# Li_Test.net
KiCad netlist of a schematic drawn in Altium Designer
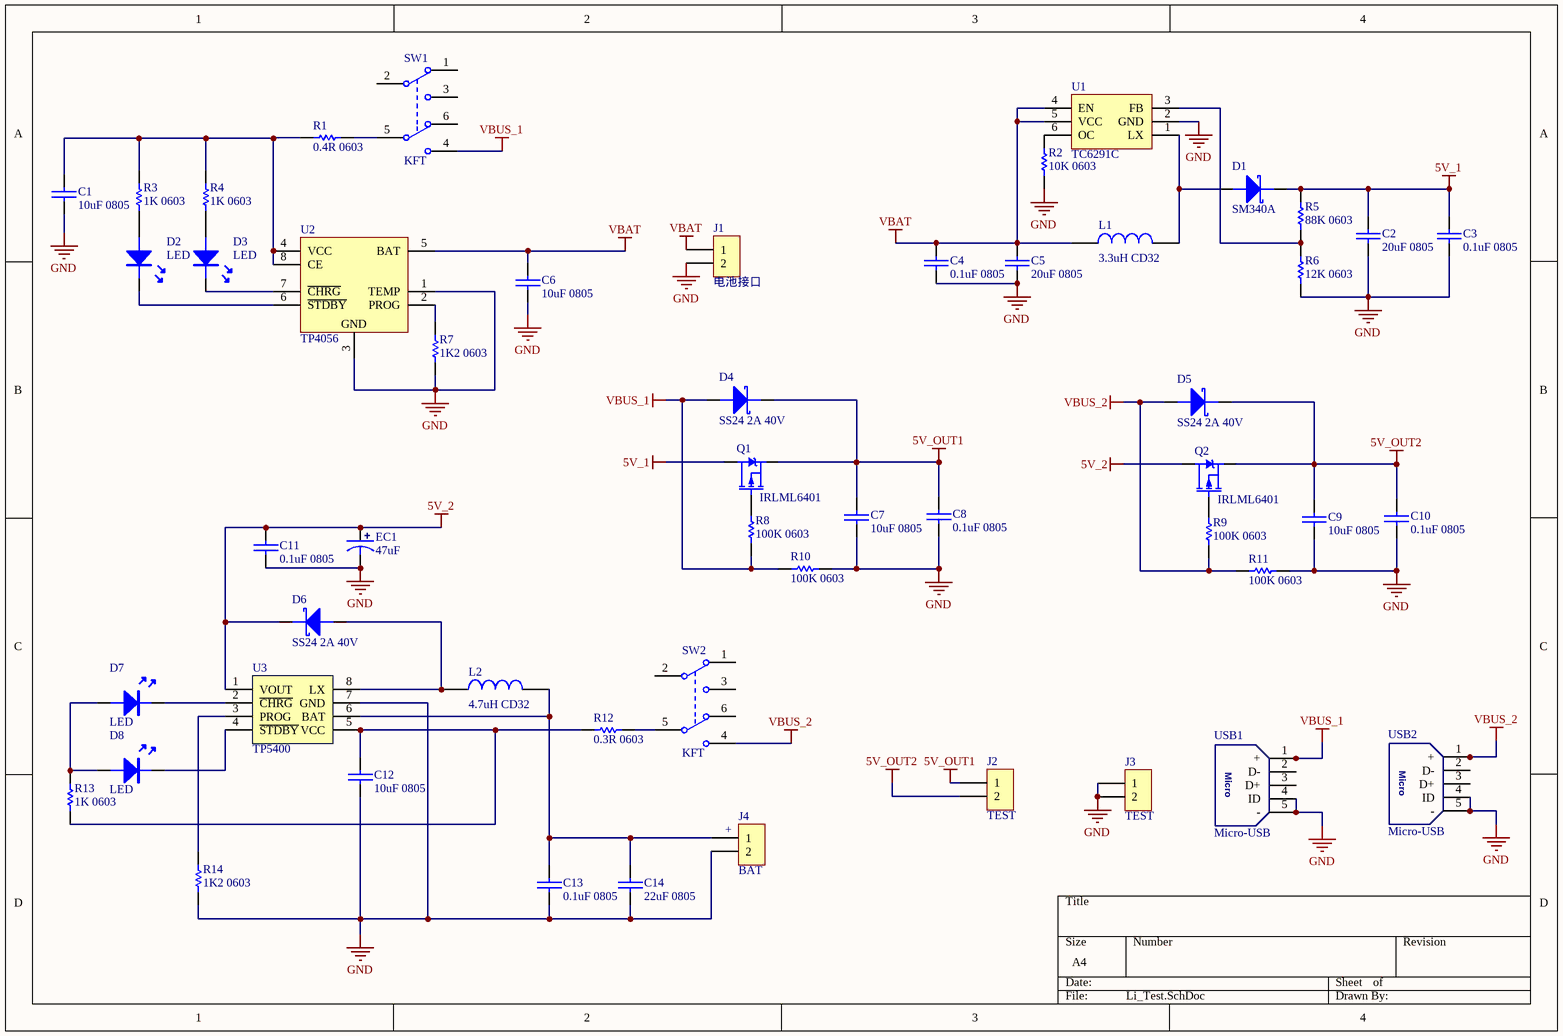
[diagram p0: Li_Test.SchDoc]

(export (version "E")
  (design (tool "Eeschema 10.0.6"))
  (components
    (comp (ref "C1")
      (value "10uF 0805")
      (footprint "0805C")
      (description "无极性电容")
      (libsource (lib "电容") (part "CAP"))
    )
    (comp (ref "C2")
      (value "20uF 0805")
      (footprint "0805C")
      (description "无极性电容")
      (libsource (lib "电容") (part "CAP"))
    )
    (comp (ref "C3")
      (value "0.1uF 0805")
      (footprint "0805C")
      (description "无极性电容")
      (libsource (lib "电容") (part "CAP"))
    )
    (comp (ref "C4")
      (value "0.1uF 0805")
      (footprint "0805C")
      (description "无极性电容")
      (libsource (lib "电容") (part "CAP"))
    )
    (comp (ref "C5")
      (value "20uF 0805")
      (footprint "0805C")
      (description "无极性电容")
      (libsource (lib "电容") (part "CAP"))
    )
    (comp (ref "C6")
      (value "10uF 0805")
      (footprint "0805C")
      (description "无极性电容")
      (libsource (lib "电容") (part "CAP"))
    )
    (comp (ref "C7")
      (value "10uF 0805")
      (footprint "0805C")
      (description "无极性电容")
      (libsource (lib "电容") (part "CAP"))
    )
    (comp (ref "C8")
      (value "0.1uF 0805")
      (footprint "0805C")
      (description "无极性电容")
      (libsource (lib "电容") (part "CAP"))
    )
    (comp (ref "C9")
      (value "10uF 0805")
      (footprint "0805C")
      (description "无极性电容")
      (libsource (lib "电容") (part "CAP"))
    )
    (comp (ref "C10")
      (value "0.1uF 0805")
      (footprint "0805C")
      (description "无极性电容")
      (libsource (lib "电容") (part "CAP"))
    )
    (comp (ref "C11")
      (value "0.1uF 0805")
      (footprint "0805C")
      (description "无极性电容")
      (libsource (lib "电容") (part "CAP"))
    )
    (comp (ref "C12")
      (value "10uF 0805")
      (footprint "0805C")
      (description "无极性电容")
      (libsource (lib "电容") (part "CAP"))
    )
    (comp (ref "C13")
      (value "0.1uF 0805")
      (footprint "0805C")
      (description "无极性电容")
      (libsource (lib "电容") (part "CAP"))
    )
    (comp (ref "C14")
      (value "22uF 0805")
      (footprint "0805C")
      (description "无极性电容")
      (libsource (lib "电容") (part "CAP"))
    )
    (comp (ref "D1")
      (value "SM340A")
      (footprint "SMA/DO-214AC")
      (description "肖特基二极管")
      (libsource (lib "二极管") (part "DIODE SCHOTTKY"))
    )
    (comp (ref "D2") (value "LED") (footprint "LED-0805G") (libsource (lib "LED") (part "LED")))
    (comp (ref "D3") (value "LED") (footprint "LED-0805R") (libsource (lib "LED") (part "LED")))
    (comp (ref "D4")
      (value "SS24 2A 40V")
      (footprint "SMA/DO-214AC")
      (description "肖特基二极管")
      (libsource (lib "二极管") (part "DIODE SCHOTTKY"))
    )
    (comp (ref "D5")
      (value "SS24 2A 40V")
      (footprint "SMA/DO-214AC")
      (description "肖特基二极管")
      (libsource (lib "二极管") (part "DIODE SCHOTTKY"))
    )
    (comp (ref "D6")
      (value "SS24 2A 40V")
      (footprint "SMA/DO-214AC")
      (description "肖特基二极管")
      (libsource (lib "二极管") (part "DIODE SCHOTTKY"))
    )
    (comp (ref "D7") (value "LED") (footprint "LED-0805R") (libsource (lib "LED") (part "LED")))
    (comp (ref "D8") (value "LED") (footprint "LED-0805G") (libsource (lib "LED") (part "LED")))
    (comp (ref "EC1")
      (value "47uF")
      (footprint "SMD-EC4.0X4.3X5.4")
      (description "贴片电解电容")
      (libsource (lib "电容") (part "SMD_ECAP"))
    )
    (comp (ref "J1")
      (value "电池接口")
      (footprint "Fe-HDR1X2/2.54-S")
      (libsource (lib "排母") (part "Female HDR1X2"))
    )
    (comp (ref "J2")
      (value "TEST")
      (footprint "Fe-HDR1X2/2.54-S")
      (libsource (lib "排母") (part "Female HDR1X2"))
    )
    (comp (ref "J3")
      (value "TEST")
      (footprint "Fe-HDR1X2/2.54-S")
      (libsource (lib "排母") (part "Female HDR1X2"))
    )
    (comp (ref "J4")
      (value "BAT")
      (footprint "Fe-HDR1X2/2.54-S")
      (libsource (lib "排母") (part "Female HDR1X2"))
    )
    (comp (ref "L1")
      (value "3.3uH CD32")
      (footprint "CD32")
      (description "INDUCTOR")
      (libsource (lib "电感") (part "INDUCTOR"))
    )
    (comp (ref "L2")
      (value "4.7uH CD32")
      (footprint "CD32")
      (description "INDUCTOR")
      (libsource (lib "电感") (part "INDUCTOR"))
    )
    (comp (ref "Q1")
      (value "IRLML6401")
      (footprint "SOT23")
      (description "P沟道场效应管")
      (libsource (lib "MOS管") (part "P-MOS"))
    )
    (comp (ref "Q2")
      (value "IRLML6401")
      (footprint "SOT23")
      (description "P沟道场效应管")
      (libsource (lib "MOS管") (part "P-MOS"))
    )
    (comp (ref "R1") (value "0.4R 0603") (footprint "0603R") (libsource (lib "电阻") (part "RES")))
    (comp (ref "R2") (value "10K 0603") (footprint "0603R") (libsource (lib "电阻") (part "RES")))
    (comp (ref "R3") (value "1K 0603") (footprint "0603R") (libsource (lib "电阻") (part "RES")))
    (comp (ref "R4") (value "1K 0603") (footprint "0603R") (libsource (lib "电阻") (part "RES")))
    (comp (ref "R5") (value "88K 0603") (footprint "0603R") (libsource (lib "电阻") (part "RES")))
    (comp (ref "R6") (value "12K 0603") (footprint "0603R") (libsource (lib "电阻") (part "RES")))
    (comp (ref "R7") (value "1K2 0603") (footprint "0603R") (libsource (lib "电阻") (part "RES")))
    (comp (ref "R8") (value "100K 0603") (footprint "0603R") (libsource (lib "电阻") (part "RES")))
    (comp (ref "R9") (value "100K 0603") (footprint "0603R") (libsource (lib "电阻") (part "RES")))
    (comp (ref "R10") (value "100K 0603") (footprint "0603R") (libsource (lib "电阻") (part "RES")))
    (comp (ref "R11") (value "100K 0603") (footprint "0603R") (libsource (lib "电阻") (part "RES")))
    (comp (ref "R12") (value "0.3R 0603") (footprint "0603R") (libsource (lib "电阻") (part "RES")))
    (comp (ref "R13") (value "1K 0603") (footprint "0603R") (libsource (lib "电阻") (part "RES")))
    (comp (ref "R14") (value "1K2 0603") (footprint "0603R") (libsource (lib "电阻") (part "RES")))
    (comp (ref "SW1")
      (value "KFT")
      (footprint "KFT DIP-7X7")
      (description "Self-locking Switch")
      (libsource (lib "Li_Test") (part "KFT_7X7-DIP"))
    )
    (comp (ref "SW2")
      (value "KFT")
      (footprint "KFT DIP-7X7")
      (description "Self-locking Switch")
      (libsource (lib "Li_Test") (part "KFT_7X7-DIP"))
    )
    (comp (ref "U1")
      (value "TC6291C")
      (footprint "SOT23-6")
      (description "DC-DC升压IC")
      (libsource (lib "Li_Test") (part "TC6291C"))
    )
    (comp (ref "U2") (value "TP4056") (footprint "SOP8") (libsource (lib "电源芯片") (part "TP4056")))
    (comp (ref "U3") (value "TP5400") (footprint "SOIC8") (libsource (lib "Li_Test") (part "TP5400")))
    (comp (ref "USB1")
      (value "Micro-USB")
      (footprint "USB-micro_C")
      (libsource (lib "USB") (part "Micro-USB"))
    )
    (comp (ref "USB2")
      (value "Micro-USB")
      (footprint "USB-micro_C")
      (libsource (lib "USB") (part "Micro-USB"))
    )
  )
  (nets
    (net (code "1") (name "5V_1") (class "Default")
      (node (ref "C2") (pin "2") (pinfunction "2_2") (pintype "passive"))
      (node (ref "C3") (pin "2") (pinfunction "2_2") (pintype "passive"))
      (node (ref "D1") (pin "K") (pinfunction "K_K") (pintype "passive"))
      (node (ref "Q1") (pin "D") (pinfunction "D_D") (pintype "passive"))
      (node (ref "R5") (pin "2") (pinfunction "2_2") (pintype "passive"))
    )
    (net (code "2") (name "5V_2") (class "Default")
      (node (ref "C11") (pin "2") (pinfunction "2_2") (pintype "passive"))
      (node (ref "D6") (pin "K") (pinfunction "K_K") (pintype "passive"))
      (node (ref "EC1") (pin "1") (pinfunction "1_1") (pintype "passive"))
      (node (ref "Q2") (pin "D") (pinfunction "D_D") (pintype "passive"))
      (node (ref "U3") (pin "1") (pinfunction "VOUT_1") (pintype "passive"))
    )
    (net (code "3") (name "5V_OUT1") (class "Default")
      (node (ref "C7") (pin "1") (pinfunction "1_1") (pintype "passive"))
      (node (ref "C8") (pin "1") (pinfunction "1_1") (pintype "passive"))
      (node (ref "D4") (pin "K") (pinfunction "K_K") (pintype "passive"))
      (node (ref "J2") (pin "1") (pinfunction "1_1") (pintype "passive"))
      (node (ref "Q1") (pin "S") (pinfunction "S_S") (pintype "passive"))
    )
    (net (code "4") (name "5V_OUT2") (class "Default")
      (node (ref "C10") (pin "1") (pinfunction "1_1") (pintype "passive"))
      (node (ref "C9") (pin "1") (pinfunction "1_1") (pintype "passive"))
      (node (ref "D5") (pin "K") (pinfunction "K_K") (pintype "passive"))
      (node (ref "J2") (pin "2") (pinfunction "2_2") (pintype "passive"))
      (node (ref "Q2") (pin "S") (pinfunction "S_S") (pintype "passive"))
    )
    (net (code "5") (name "GND") (class "Default")
      (node (ref "C1") (pin "1") (pinfunction "1_1") (pintype "passive"))
      (node (ref "C10") (pin "2") (pinfunction "2_2") (pintype "passive"))
      (node (ref "C11") (pin "1") (pinfunction "1_1") (pintype "passive"))
      (node (ref "C12") (pin "1") (pinfunction "1_1") (pintype "passive"))
      (node (ref "C13") (pin "1") (pinfunction "1_1") (pintype "passive"))
      (node (ref "C14") (pin "1") (pinfunction "1_1") (pintype "passive"))
      (node (ref "C2") (pin "1") (pinfunction "1_1") (pintype "passive"))
      (node (ref "C3") (pin "1") (pinfunction "1_1") (pintype "passive"))
      (node (ref "C4") (pin "1") (pinfunction "1_1") (pintype "passive"))
      (node (ref "C5") (pin "1") (pinfunction "1_1") (pintype "passive"))
      (node (ref "C6") (pin "2") (pinfunction "2_2") (pintype "passive"))
      (node (ref "C7") (pin "2") (pinfunction "2_2") (pintype "passive"))
      (node (ref "C8") (pin "2") (pinfunction "2_2") (pintype "passive"))
      (node (ref "C9") (pin "2") (pinfunction "2_2") (pintype "passive"))
      (node (ref "EC1") (pin "2") (pinfunction "2_2") (pintype "passive"))
      (node (ref "J1") (pin "2") (pinfunction "2_2") (pintype "passive"))
      (node (ref "J3") (pin "1") (pinfunction "1_1") (pintype "passive"))
      (node (ref "J3") (pin "2") (pinfunction "2_2") (pintype "passive"))
      (node (ref "J4") (pin "2") (pinfunction "2_2") (pintype "passive"))
      (node (ref "R10") (pin "1") (pinfunction "1_1") (pintype "passive"))
      (node (ref "R11") (pin "1") (pinfunction "1_1") (pintype "passive"))
      (node (ref "R14") (pin "2") (pinfunction "2_2") (pintype "passive"))
      (node (ref "R2") (pin "1") (pinfunction "1_1") (pintype "passive"))
      (node (ref "R6") (pin "1") (pinfunction "1_1") (pintype "passive"))
      (node (ref "R7") (pin "2") (pinfunction "2_2") (pintype "passive"))
      (node (ref "U1") (pin "2") (pinfunction "GND_2") (pintype "passive"))
      (node (ref "U2") (pin "1") (pinfunction "TEMP_1") (pintype "passive"))
      (node (ref "U2") (pin "3") (pinfunction "GND_3") (pintype "passive"))
      (node (ref "U3") (pin "7") (pinfunction "GND_7") (pintype "passive"))
      (node (ref "USB1") (pin "4") (pinfunction "ID_4") (pintype "passive"))
      (node (ref "USB1") (pin "5") (pinfunction "-_5") (pintype "passive"))
      (node (ref "USB2") (pin "4") (pinfunction "ID_4") (pintype "passive"))
      (node (ref "USB2") (pin "5") (pinfunction "-_5") (pintype "passive"))
    )
    (net (code "6") (name "Net-(D2-PadA)") (class "Default")
      (node (ref "D2") (pin "A") (pinfunction "A_A") (pintype "passive"))
      (node (ref "R3") (pin "2") (pinfunction "2_2") (pintype "passive"))
    )
    (net (code "7") (name "Net-(D3-PadA)") (class "Default")
      (node (ref "D3") (pin "A") (pinfunction "A_A") (pintype "passive"))
      (node (ref "R4") (pin "2") (pinfunction "2_2") (pintype "passive"))
    )
    (net (code "8") (name "Net-(D7-PadA)") (class "Default")
      (node (ref "D7") (pin "A") (pinfunction "A_A") (pintype "passive"))
      (node (ref "D8") (pin "A") (pinfunction "A_A") (pintype "passive"))
      (node (ref "R13") (pin "2") (pinfunction "2_2") (pintype "passive"))
    )
    (net (code "9") (name "Net-(Q1-PadG)") (class "Default")
      (node (ref "Q1") (pin "G") (pinfunction "G_G") (pintype "passive"))
      (node (ref "R8") (pin "1") (pinfunction "1_1") (pintype "passive"))
    )
    (net (code "10") (name "Net-(Q2-PadG)") (class "Default")
      (node (ref "Q2") (pin "G") (pinfunction "G_G") (pintype "passive"))
      (node (ref "R9") (pin "1") (pinfunction "1_1") (pintype "passive"))
    )
    (net (code "11") (name "Net-(R1-Pad1)") (class "Default")
      (node (ref "R1") (pin "1") (pinfunction "1_1") (pintype "passive"))
      (node (ref "SW1") (pin "5") (pinfunction "COM2_5") (pintype "passive"))
    )
    (net (code "12") (name "Net-(R12-Pad1)") (class "Default")
      (node (ref "R12") (pin "1") (pinfunction "1_1") (pintype "passive"))
      (node (ref "SW2") (pin "5") (pinfunction "COM2_5") (pintype "passive"))
    )
    (net (code "13") (name "Net-(U1-FB)") (class "Default")
      (node (ref "R5") (pin "1") (pinfunction "1_1") (pintype "passive"))
      (node (ref "R6") (pin "2") (pinfunction "2_2") (pintype "passive"))
      (node (ref "U1") (pin "3") (pinfunction "FB_3") (pintype "passive"))
    )
    (net (code "14") (name "Net-(U1-LX)") (class "Default")
      (node (ref "D1") (pin "A") (pinfunction "A_A") (pintype "passive"))
      (node (ref "L1") (pin "2") (pinfunction "2_2") (pintype "passive"))
      (node (ref "U1") (pin "1") (pinfunction "LX_1") (pintype "passive"))
    )
    (net (code "15") (name "Net-(U1-OC)") (class "Default")
      (node (ref "R2") (pin "2") (pinfunction "2_2") (pintype "passive"))
      (node (ref "U1") (pin "6") (pinfunction "OC_6") (pintype "passive"))
    )
    (net (code "16") (name "Net-(U2-CE)") (class "Default")
      (node (ref "C1") (pin "2") (pinfunction "2_2") (pintype "passive"))
      (node (ref "R1") (pin "2") (pinfunction "2_2") (pintype "passive"))
      (node (ref "R3") (pin "1") (pinfunction "1_1") (pintype "passive"))
      (node (ref "R4") (pin "1") (pinfunction "1_1") (pintype "passive"))
      (node (ref "U2") (pin "4") (pinfunction "VCC_4") (pintype "passive"))
      (node (ref "U2") (pin "8") (pinfunction "CE_8") (pintype "passive"))
    )
    (net (code "17") (name "Net-(U2-PROG)") (class "Default")
      (node (ref "R7") (pin "1") (pinfunction "1_1") (pintype "passive"))
      (node (ref "U2") (pin "2") (pinfunction "PROG_2") (pintype "passive"))
    )
    (net (code "18") (name "Net-(U2-~{CHRG})") (class "Default")
      (node (ref "D3") (pin "K") (pinfunction "K_K") (pintype "passive"))
      (node (ref "U2") (pin "7") (pinfunction "~{CHRG}_7") (pintype "passive"))
    )
    (net (code "19") (name "Net-(U2-~{STDBY})") (class "Default")
      (node (ref "D2") (pin "K") (pinfunction "K_K") (pintype "passive"))
      (node (ref "U2") (pin "6") (pinfunction "~{STDBY}_6") (pintype "passive"))
    )
    (net (code "20") (name "Net-(U3-BAT)") (class "Default")
      (node (ref "C13") (pin "2") (pinfunction "2_2") (pintype "passive"))
      (node (ref "C14") (pin "2") (pinfunction "2_2") (pintype "passive"))
      (node (ref "J4") (pin "1") (pinfunction "1_1") (pintype "passive"))
      (node (ref "L2") (pin "2") (pinfunction "2_2") (pintype "passive"))
      (node (ref "U3") (pin "6") (pinfunction "BAT_6") (pintype "passive"))
    )
    (net (code "21") (name "Net-(U3-LX)") (class "Default")
      (node (ref "D6") (pin "A") (pinfunction "A_A") (pintype "passive"))
      (node (ref "L2") (pin "1") (pinfunction "1_1") (pintype "passive"))
      (node (ref "U3") (pin "8") (pinfunction "LX_8") (pintype "passive"))
    )
    (net (code "22") (name "Net-(U3-PROG)") (class "Default")
      (node (ref "R14") (pin "1") (pinfunction "1_1") (pintype "passive"))
      (node (ref "U3") (pin "3") (pinfunction "PROG_3") (pintype "passive"))
    )
    (net (code "23") (name "Net-(U3-VCC)") (class "Default")
      (node (ref "C12") (pin "2") (pinfunction "2_2") (pintype "passive"))
      (node (ref "R12") (pin "2") (pinfunction "2_2") (pintype "passive"))
      (node (ref "R13") (pin "1") (pinfunction "1_1") (pintype "passive"))
      (node (ref "U3") (pin "5") (pinfunction "VCC_5") (pintype "passive"))
    )
    (net (code "24") (name "Net-(U3-~{CHRG})") (class "Default")
      (node (ref "D7") (pin "K") (pinfunction "K_K") (pintype "passive"))
      (node (ref "U3") (pin "2") (pinfunction "~{CHRG}_2") (pintype "passive"))
    )
    (net (code "25") (name "Net-(U3-~{STDBY})") (class "Default")
      (node (ref "D8") (pin "K") (pinfunction "K_K") (pintype "passive"))
      (node (ref "U3") (pin "4") (pinfunction "~{STDBY}_4") (pintype "passive"))
    )
    (net (code "26") (name "VBAT") (class "Default")
      (node (ref "C4") (pin "2") (pinfunction "2_2") (pintype "passive"))
      (node (ref "C5") (pin "2") (pinfunction "2_2") (pintype "passive"))
      (node (ref "C6") (pin "1") (pinfunction "1_1") (pintype "passive"))
      (node (ref "J1") (pin "1") (pinfunction "1_1") (pintype "passive"))
      (node (ref "L1") (pin "1") (pinfunction "1_1") (pintype "passive"))
      (node (ref "U1") (pin "4") (pinfunction "EN_4") (pintype "passive"))
      (node (ref "U1") (pin "5") (pinfunction "VCC_5") (pintype "passive"))
      (node (ref "U2") (pin "5") (pinfunction "BAT_5") (pintype "passive"))
    )
    (net (code "27") (name "VBUS_1") (class "Default")
      (node (ref "D4") (pin "A") (pinfunction "A_A") (pintype "passive"))
      (node (ref "R10") (pin "2") (pinfunction "2_2") (pintype "passive"))
      (node (ref "R8") (pin "2") (pinfunction "2_2") (pintype "passive"))
      (node (ref "SW1") (pin "4") (pinfunction "NO2_4") (pintype "passive"))
      (node (ref "USB1") (pin "1") (pinfunction "+_1") (pintype "passive"))
    )
    (net (code "28") (name "VBUS_2") (class "Default")
      (node (ref "D5") (pin "A") (pinfunction "A_A") (pintype "passive"))
      (node (ref "R11") (pin "2") (pinfunction "2_2") (pintype "passive"))
      (node (ref "R9") (pin "2") (pinfunction "2_2") (pintype "passive"))
      (node (ref "SW2") (pin "4") (pinfunction "NO2_4") (pintype "passive"))
      (node (ref "USB2") (pin "1") (pinfunction "+_1") (pintype "passive"))
    )
    (net (code "29") (name "unconnected-(SW1-COM2-Pad2)") (class "Default")
      (node (ref "SW1") (pin "2") (pinfunction "COM2_2") (pintype "passive"))
    )
    (net (code "30") (name "unconnected-(SW1-NC1-Pad1)") (class "Default")
      (node (ref "SW1") (pin "1") (pinfunction "NC1_1") (pintype "passive"))
    )
    (net (code "31") (name "unconnected-(SW1-NC2-Pad6)") (class "Default")
      (node (ref "SW1") (pin "6") (pinfunction "NC2_6") (pintype "passive"))
    )
    (net (code "32") (name "unconnected-(SW1-NO1-Pad3)") (class "Default")
      (node (ref "SW1") (pin "3") (pinfunction "NO1_3") (pintype "passive"))
    )
    (net (code "33") (name "unconnected-(SW2-COM2-Pad2)") (class "Default")
      (node (ref "SW2") (pin "2") (pinfunction "COM2_2") (pintype "passive"))
    )
    (net (code "34") (name "unconnected-(SW2-NC1-Pad1)") (class "Default")
      (node (ref "SW2") (pin "1") (pinfunction "NC1_1") (pintype "passive"))
    )
    (net (code "35") (name "unconnected-(SW2-NC2-Pad6)") (class "Default")
      (node (ref "SW2") (pin "6") (pinfunction "NC2_6") (pintype "passive"))
    )
    (net (code "36") (name "unconnected-(SW2-NO1-Pad3)") (class "Default")
      (node (ref "SW2") (pin "3") (pinfunction "NO1_3") (pintype "passive"))
    )
    (net (code "37") (name "unconnected-(USB1-D+-Pad3)") (class "Default")
      (node (ref "USB1") (pin "3") (pinfunction "D+_3") (pintype "passive"))
    )
    (net (code "38") (name "unconnected-(USB1-D--Pad2)") (class "Default")
      (node (ref "USB1") (pin "2") (pinfunction "D-_2") (pintype "passive"))
    )
    (net (code "39") (name "unconnected-(USB2-D+-Pad3)") (class "Default")
      (node (ref "USB2") (pin "3") (pinfunction "D+_3") (pintype "passive"))
    )
    (net (code "40") (name "unconnected-(USB2-D--Pad2)") (class "Default")
      (node (ref "USB2") (pin "2") (pinfunction "D-_2") (pintype "passive"))
    )
  )
)
